# 6_-_CH340C.net
KiCad netlist of a schematic drawn in Altium Designer
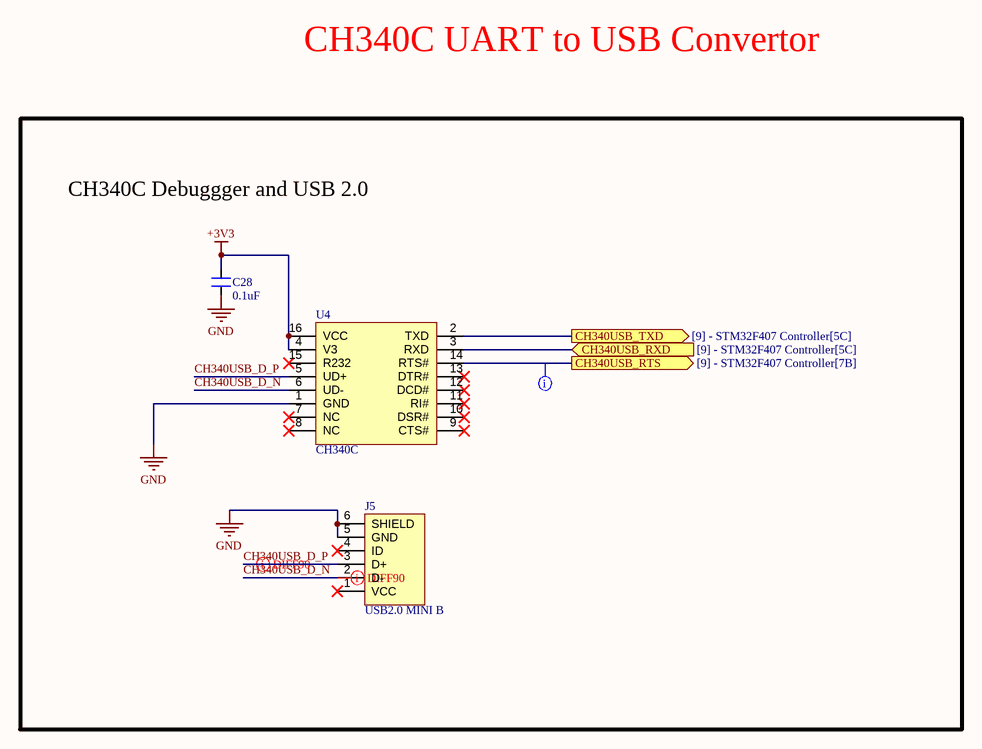
[diagram p0: [6] - CH340C.SchDoc]

(export (version "E")
  (design (tool "Eeschema 10.0.6"))
  (components
    (comp (ref "C28")
      (value "0.1uF")
      (footprint "CAP_0805")
      (description "0.1µF ±10% 50V Ceramic Capacitor X7R 0805 (2012 Metric)")
      (fields
        (field (name "MANUFACTURER") "Samsung")
        (field (name "MANUFACTURER PART NUMBER") "CL21B104KBCNNNC")
      )
      (libsource (lib "ESTEEMPCBLIB") (part "CAP_0.1uF-50V-10%-0805"))
    )
    (comp (ref "J5")
      (value "USB2.0 MINI B")
      (footprint "CON_690-005-299-043")
      (description "USB - mini B USB 2.0 Receptacle Connector 5 Position Surface Mount, Right Angle")
      (fields
        (field (name "MANUFACTURER") "EDAC")
        (field (name "MANUFACTURER PART NUMBER") "690-005-299-043")
      )
      (libsource (lib "ESTEEMPCBLIB") (part "CON_USB2.0-MINIB-SMD"))
    )
    (comp (ref "U4")
      (value "CH340C")
      (footprint "SOIC16_50_284_25X90_SMT")
      (description "USB Bridge, USB to UART USB 2.0 UART Interface")
      (fields (field (name "MANUFACTURER") "Olimex"))
      (libsource (lib "ESTEEMPCBLIB") (part "IC_CH340C"))
    )
  )
  (nets
    (net (code "1") (name "+3V3") (class "Default")
      (node (ref "C28") (pin "2") (pinfunction "2_2") (pintype "passive"))
      (node (ref "U4") (pin "16") (pinfunction "VCC_16") (pintype "passive"))
      (node (ref "U4") (pin "4") (pinfunction "V3_4") (pintype "passive"))
    )
    (net (code "2") (name "/CH340USB_D_N") (class "Default")
      (node (ref "J5") (pin "2") (pinfunction "D-_2") (pintype "passive"))
      (node (ref "U4") (pin "6") (pinfunction "UD-_6") (pintype "passive"))
    )
    (net (code "3") (name "/CH340USB_D_P") (class "Default")
      (node (ref "J5") (pin "3") (pinfunction "D+_3") (pintype "passive"))
      (node (ref "U4") (pin "5") (pinfunction "UD+_5") (pintype "passive"))
    )
    (net (code "4") (name "/CH340USB_RTS") (class "Default")
      (node (ref "U4") (pin "14") (pinfunction "RTS#_14") (pintype "passive"))
    )
    (net (code "5") (name "/CH340USB_RXD") (class "Default")
      (node (ref "U4") (pin "3") (pinfunction "RXD_3") (pintype "passive"))
    )
    (net (code "6") (name "/CH340USB_TXD") (class "Default")
      (node (ref "U4") (pin "2") (pinfunction "TXD_2") (pintype "passive"))
    )
    (net (code "7") (name "GND") (class "Default")
      (node (ref "C28") (pin "1") (pinfunction "1_1") (pintype "passive"))
      (node (ref "J5") (pin "5") (pinfunction "GND_5") (pintype "passive"))
      (node (ref "J5") (pin "6") (pinfunction "SHIELD_6") (pintype "passive"))
      (node (ref "U4") (pin "1") (pinfunction "GND_1") (pintype "passive"))
    )
    (net (code "8") (name "unconnected-(J5-ID-Pad4)") (class "Default")
      (node (ref "J5") (pin "4") (pinfunction "ID_4") (pintype "passive+no_connect"))
    )
    (net (code "9") (name "unconnected-(J5-VCC-Pad1)") (class "Default")
      (node (ref "J5") (pin "1") (pinfunction "VCC_1") (pintype "passive+no_connect"))
    )
    (net (code "10") (name "unconnected-(U4-CTS#-Pad9)") (class "Default")
      (node (ref "U4") (pin "9") (pinfunction "CTS#_9") (pintype "passive+no_connect"))
    )
    (net (code "11") (name "unconnected-(U4-DCD#-Pad12)") (class "Default")
      (node (ref "U4") (pin "12") (pinfunction "DCD#_12") (pintype "passive+no_connect"))
    )
    (net (code "12") (name "unconnected-(U4-DSR#-Pad10)") (class "Default")
      (node (ref "U4") (pin "10") (pinfunction "DSR#_10") (pintype "passive+no_connect"))
    )
    (net (code "13") (name "unconnected-(U4-DTR#-Pad13)") (class "Default")
      (node (ref "U4") (pin "13") (pinfunction "DTR#_13") (pintype "passive+no_connect"))
    )
    (net (code "14") (name "unconnected-(U4-NC-Pad7)") (class "Default")
      (node (ref "U4") (pin "7") (pinfunction "NC_7") (pintype "passive+no_connect"))
    )
    (net (code "15") (name "unconnected-(U4-NC-Pad8)") (class "Default")
      (node (ref "U4") (pin "8") (pinfunction "NC_8") (pintype "passive+no_connect"))
    )
    (net (code "16") (name "unconnected-(U4-R232-Pad15)") (class "Default")
      (node (ref "U4") (pin "15") (pinfunction "R232_15") (pintype "passive+no_connect"))
    )
    (net (code "17") (name "unconnected-(U4-RI#-Pad11)") (class "Default")
      (node (ref "U4") (pin "11") (pinfunction "RI#_11") (pintype "passive+no_connect"))
    )
  )
)
